# TEST_CPU.net
KiCad netlist of a schematic drawn in EAGLE
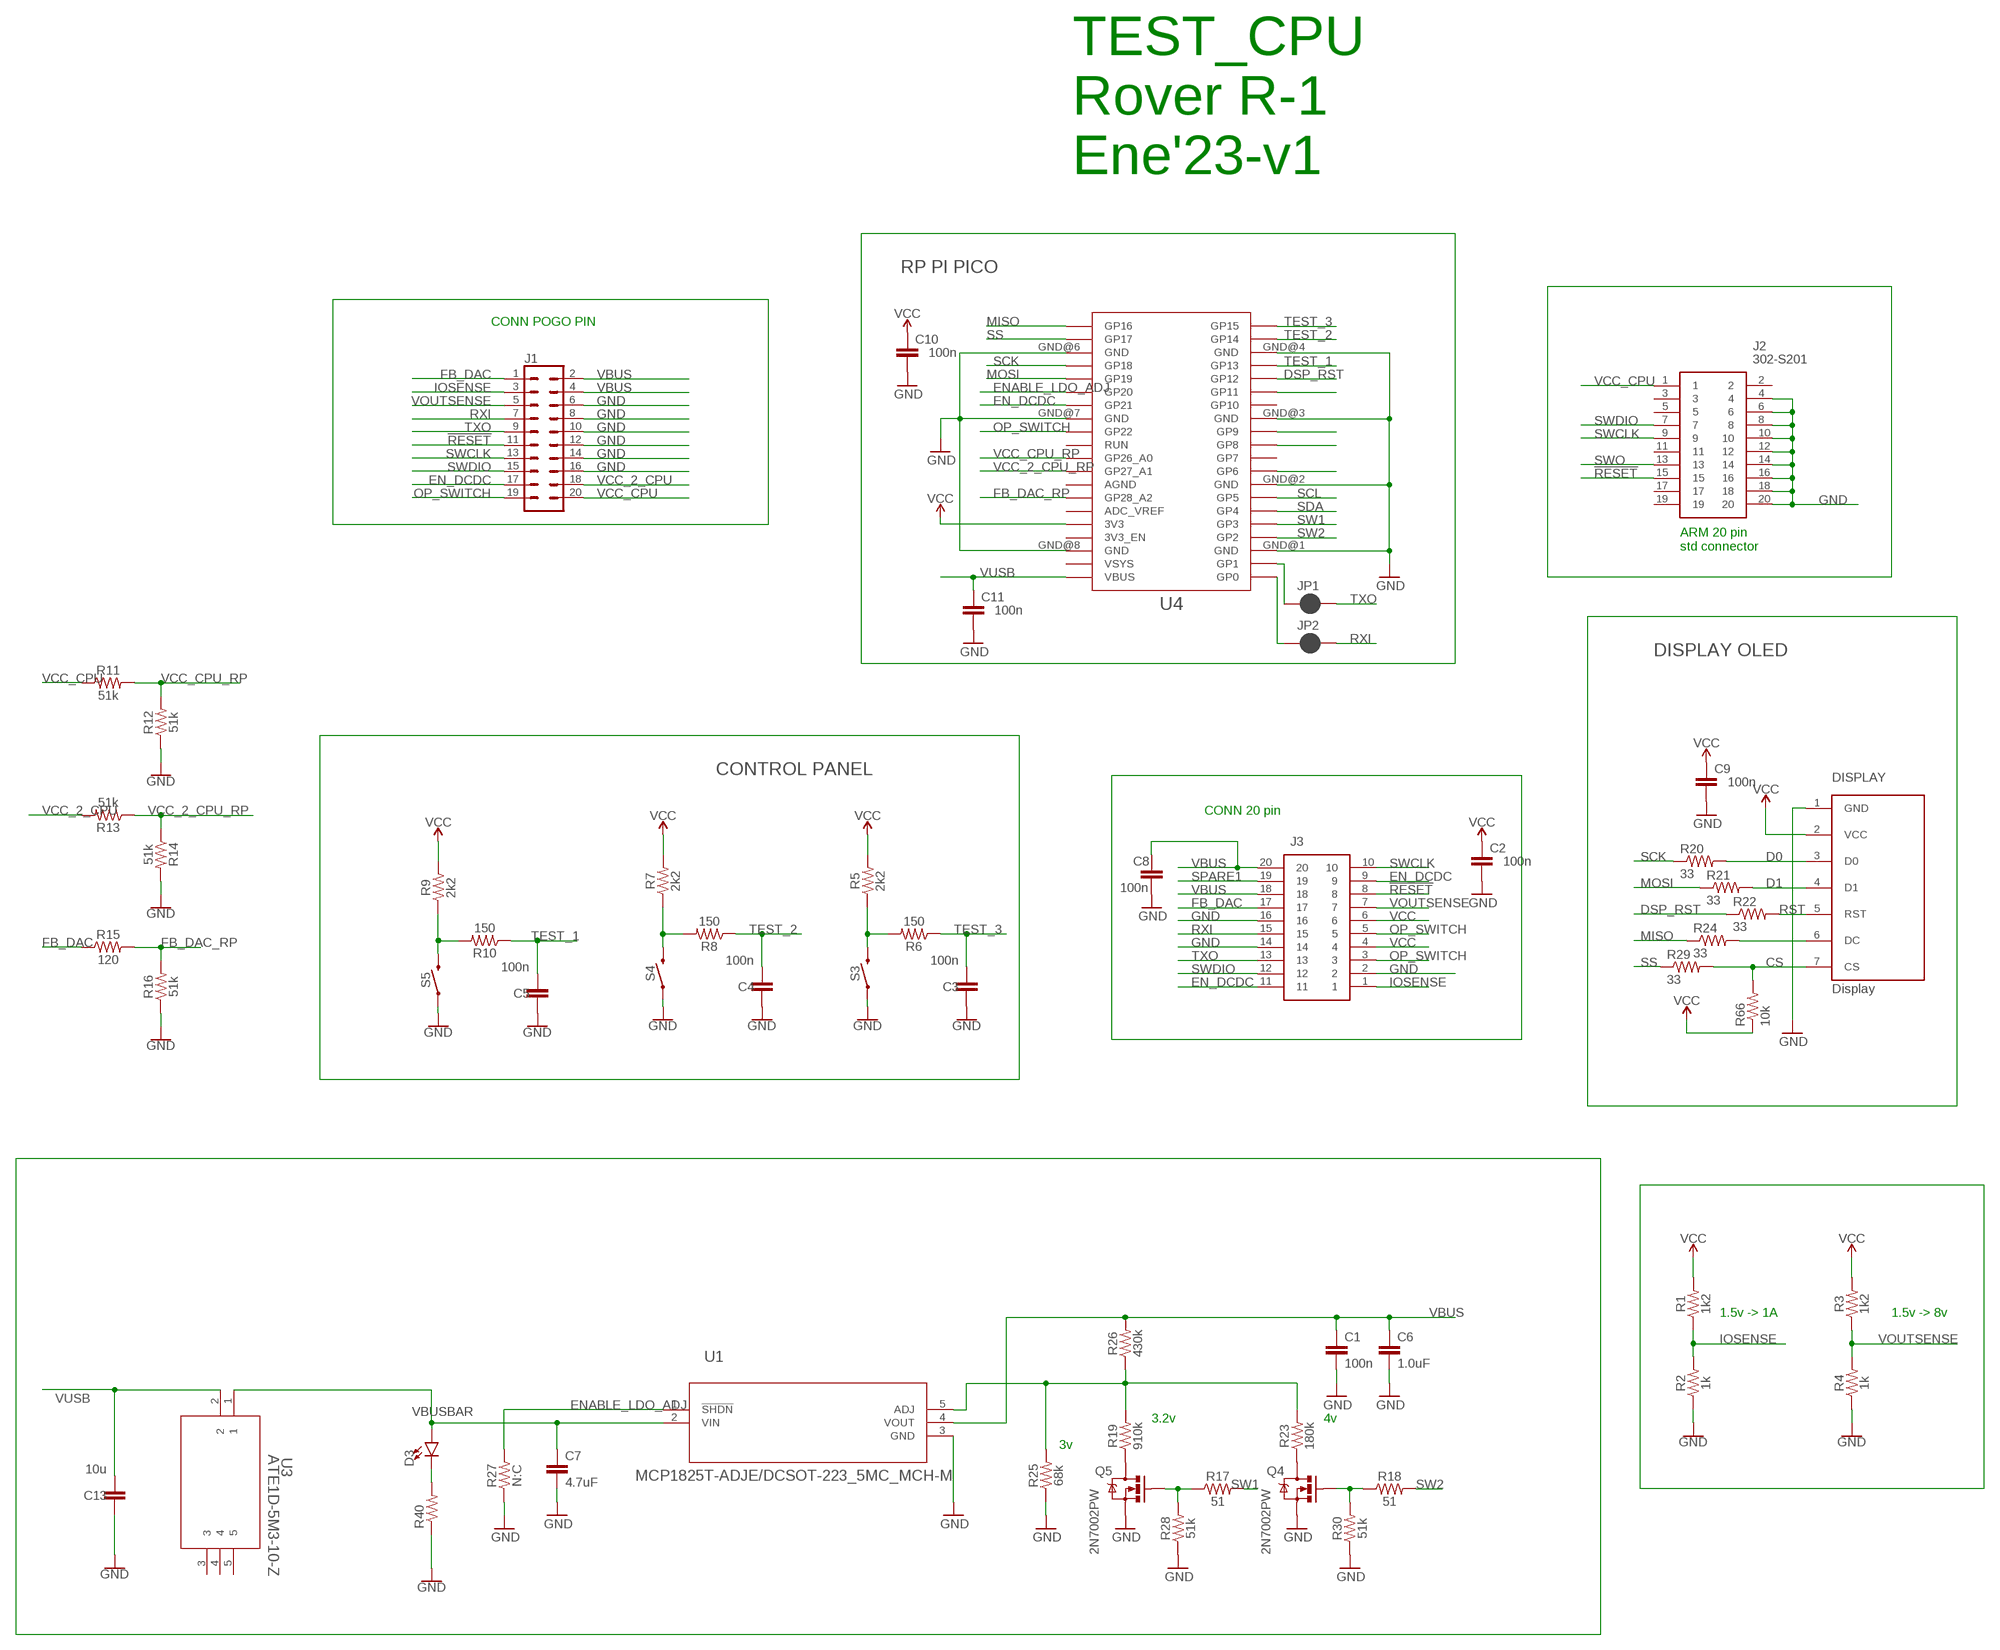
[diagram p0: schematic, sheet 1]

(export (version "E")
  (design (tool "Eeschema 10.0.6"))
  (components
    (comp (ref "C1")
      (value "100n")
      (footprint "eagle-import:0805")
      (libsource (lib "eagle-import") (part "1.0UF-0805-25V-(+80/-20%)"))
    )
    (comp (ref "C2")
      (value "100n")
      (footprint "eagle-import:0805")
      (libsource (lib "eagle-import") (part "1.0UF-0805-25V-(+80/-20%)"))
    )
    (comp (ref "C3")
      (value "100n")
      (footprint "eagle-import:0805")
      (libsource (lib "eagle-import") (part "1.0UF-0805-25V-(+80/-20%)"))
    )
    (comp (ref "C4")
      (value "100n")
      (footprint "eagle-import:0805")
      (libsource (lib "eagle-import") (part "1.0UF-0805-25V-(+80/-20%)"))
    )
    (comp (ref "C5")
      (value "100n")
      (footprint "eagle-import:0805")
      (libsource (lib "eagle-import") (part "1.0UF-0805-25V-(+80/-20%)"))
    )
    (comp (ref "C6")
      (value "1.0uF")
      (footprint "eagle-import:0805")
      (libsource (lib "eagle-import") (part "1.0UF-0805-25V-(+80/-20%)"))
    )
    (comp (ref "C7")
      (value "4.7uF")
      (footprint "eagle-import:0805")
      (libsource (lib "eagle-import") (part "1.0UF-0805-25V-(+80/-20%)"))
    )
    (comp (ref "C8")
      (value "100n")
      (footprint "eagle-import:0805")
      (libsource (lib "eagle-import") (part "1.0UF-0805-25V-(+80/-20%)"))
    )
    (comp (ref "C9")
      (value "100n")
      (footprint "eagle-import:0805")
      (libsource (lib "eagle-import") (part "1.0UF-0805-25V-(+80/-20%)"))
    )
    (comp (ref "C10")
      (value "100n")
      (footprint "eagle-import:0805")
      (libsource (lib "eagle-import") (part "1.0UF-0805-25V-(+80/-20%)"))
    )
    (comp (ref "C11")
      (value "100n")
      (footprint "eagle-import:0805")
      (libsource (lib "eagle-import") (part "1.0UF-0805-25V-(+80/-20%)"))
    )
    (comp (ref "C13")
      (value "10u")
      (footprint "eagle-import:0805")
      (libsource (lib "eagle-import") (part "1.0UF-0805-25V-(+80/-20%)"))
    )
    (comp (ref "D3")
      (value "LED3MM")
      (footprint "eagle-import:LED_3MM")
      (libsource (lib "eagle-import") (part "LED3MM"))
    )
    (comp (ref "DISPLAY")
      (value "Display")
      (footprint "eagle-import:OLED_LCD")
      (libsource (lib "eagle-import") (part "OLED_LCD"))
    )
    (comp (ref "J1")
      (value "CONN_10X2")
      (footprint "eagle-import:2X10")
      (libsource (lib "eagle-import") (part "CONN_10X2"))
    )
    (comp (ref "J2")
      (value "302-S201")
      (footprint "eagle-import:SHDR20W66P254_2X10_3300X905X90")
      (libsource (lib "eagle-import") (part "302-S201"))
    )
    (comp (ref "J3")
      (value "DF40C-20DP-0.4V_51_")
      (footprint "eagle-import:DF40C-20DPA")
      (fields
        (field (name "ARROW_PART_NUMBER") "DF40C-20DP-0.4V(51)")
        (field (name "MOUSER_PART_NUMBER") "798-DF40C20DP0.4V51")
      )
      (libsource (lib "eagle-import") (part "DF40C-20DP-0.4V_51_"))
    )
    (comp (ref "JP1")
      (value "JUMPER-SMT_2_NC_PASTE_SILK")
      (footprint "eagle-import:SMT-JUMPER_2_NC_PASTE_SILK")
      (libsource (lib "eagle-import") (part "JUMPER-SMT_2_NC_PASTE_SILK"))
    )
    (comp (ref "JP2")
      (value "JUMPER-SMT_2_NC_PASTE_SILK")
      (footprint "eagle-import:SMT-JUMPER_2_NC_PASTE_SILK")
      (libsource (lib "eagle-import") (part "JUMPER-SMT_2_NC_PASTE_SILK"))
    )
    (comp (ref "Q4")
      (value "2N7002PW")
      (footprint "eagle-import:SOT323")
      (libsource (lib "eagle-import") (part "MOSFET-NCHANNEL2N7002PW"))
    )
    (comp (ref "Q5")
      (value "2N7002PW")
      (footprint "eagle-import:SOT323")
      (libsource (lib "eagle-import") (part "MOSFET-NCHANNEL2N7002PW"))
    )
    (comp (ref "R1")
      (value "1k2")
      (footprint "eagle-import:0805")
      (libsource (lib "eagle-import") (part "RESISTOR0805"))
    )
    (comp (ref "R2")
      (value "1k")
      (footprint "eagle-import:0805")
      (libsource (lib "eagle-import") (part "RESISTOR0805"))
    )
    (comp (ref "R3")
      (value "1k2")
      (footprint "eagle-import:0805")
      (libsource (lib "eagle-import") (part "RESISTOR0805"))
    )
    (comp (ref "R4")
      (value "1k")
      (footprint "eagle-import:0805")
      (libsource (lib "eagle-import") (part "RESISTOR0805"))
    )
    (comp (ref "R5")
      (value "2k2")
      (footprint "eagle-import:0805")
      (libsource (lib "eagle-import") (part "RESISTOR0805"))
    )
    (comp (ref "R6")
      (value "150")
      (footprint "eagle-import:0805")
      (libsource (lib "eagle-import") (part "RESISTOR0805"))
    )
    (comp (ref "R7")
      (value "2k2")
      (footprint "eagle-import:0805")
      (libsource (lib "eagle-import") (part "RESISTOR0805"))
    )
    (comp (ref "R8")
      (value "150")
      (footprint "eagle-import:0805")
      (libsource (lib "eagle-import") (part "RESISTOR0805"))
    )
    (comp (ref "R9")
      (value "2k2")
      (footprint "eagle-import:0805")
      (libsource (lib "eagle-import") (part "RESISTOR0805"))
    )
    (comp (ref "R10")
      (value "150")
      (footprint "eagle-import:0805")
      (libsource (lib "eagle-import") (part "RESISTOR0805"))
    )
    (comp (ref "R11")
      (value "51k")
      (footprint "eagle-import:0805")
      (libsource (lib "eagle-import") (part "RESISTOR0805"))
    )
    (comp (ref "R12")
      (value "51k")
      (footprint "eagle-import:0805")
      (libsource (lib "eagle-import") (part "RESISTOR0805"))
    )
    (comp (ref "R13")
      (value "51k")
      (footprint "eagle-import:0805")
      (libsource (lib "eagle-import") (part "RESISTOR0805"))
    )
    (comp (ref "R14")
      (value "51k")
      (footprint "eagle-import:0805")
      (libsource (lib "eagle-import") (part "RESISTOR0805"))
    )
    (comp (ref "R15")
      (value "120")
      (footprint "eagle-import:0805")
      (libsource (lib "eagle-import") (part "RESISTOR0805"))
    )
    (comp (ref "R16")
      (value "51k")
      (footprint "eagle-import:0805")
      (libsource (lib "eagle-import") (part "RESISTOR0805"))
    )
    (comp (ref "R17")
      (value "51")
      (footprint "eagle-import:0805")
      (libsource (lib "eagle-import") (part "RESISTOR0805"))
    )
    (comp (ref "R18")
      (value "51")
      (footprint "eagle-import:0805")
      (libsource (lib "eagle-import") (part "RESISTOR0805"))
    )
    (comp (ref "R19")
      (value "910k")
      (footprint "eagle-import:0805")
      (libsource (lib "eagle-import") (part "RESISTOR0805"))
    )
    (comp (ref "R20")
      (value "33")
      (footprint "eagle-import:0805")
      (libsource (lib "eagle-import") (part "RESISTOR0805"))
    )
    (comp (ref "R21")
      (value "33")
      (footprint "eagle-import:0805")
      (libsource (lib "eagle-import") (part "RESISTOR0805"))
    )
    (comp (ref "R22")
      (value "33")
      (footprint "eagle-import:0805")
      (libsource (lib "eagle-import") (part "RESISTOR0805"))
    )
    (comp (ref "R23")
      (value "180k")
      (footprint "eagle-import:0805")
      (libsource (lib "eagle-import") (part "RESISTOR0805"))
    )
    (comp (ref "R24")
      (value "33")
      (footprint "eagle-import:0805")
      (libsource (lib "eagle-import") (part "RESISTOR0805"))
    )
    (comp (ref "R25")
      (value "68k")
      (footprint "eagle-import:0805")
      (libsource (lib "eagle-import") (part "RESISTOR0805"))
    )
    (comp (ref "R26")
      (value "430k")
      (footprint "eagle-import:0805")
      (libsource (lib "eagle-import") (part "RESISTOR0805"))
    )
    (comp (ref "R27")
      (value "N:C")
      (footprint "eagle-import:0805")
      (libsource (lib "eagle-import") (part "RESISTOR0805"))
    )
    (comp (ref "R28")
      (value "51k")
      (footprint "eagle-import:0805")
      (libsource (lib "eagle-import") (part "RESISTOR0805"))
    )
    (comp (ref "R29")
      (value "33")
      (footprint "eagle-import:0805")
      (libsource (lib "eagle-import") (part "RESISTOR0805"))
    )
    (comp (ref "R30")
      (value "51k")
      (footprint "eagle-import:0805")
      (libsource (lib "eagle-import") (part "RESISTOR0805"))
    )
    (comp (ref "R40")
      (value "360")
      (footprint "eagle-import:0805")
      (libsource (lib "eagle-import") (part "RESISTOR0805"))
    )
    (comp (ref "R66")
      (value "10k")
      (footprint "eagle-import:0805")
      (libsource (lib "eagle-import") (part "RESISTOR0805"))
    )
    (comp (ref "S3")
      (value "MOMENTARY-SWITCH-SPST-SMD-5.2MM")
      (footprint "eagle-import:TACTILE_SWITCH_SMD_5.2MM")
      (libsource (lib "eagle-import") (part "MOMENTARY-SWITCH-SPST-SMD-5.2MM"))
    )
    (comp (ref "S4")
      (value "MOMENTARY-SWITCH-SPST-SMD-5.2MM")
      (footprint "eagle-import:TACTILE_SWITCH_SMD_5.2MM")
      (libsource (lib "eagle-import") (part "MOMENTARY-SWITCH-SPST-SMD-5.2MM"))
    )
    (comp (ref "S5")
      (value "MOMENTARY-SWITCH-SPST-SMD-5.2MM")
      (footprint "eagle-import:TACTILE_SWITCH_SMD_5.2MM")
      (libsource (lib "eagle-import") (part "MOMENTARY-SWITCH-SPST-SMD-5.2MM"))
    )
    (comp (ref "U1")
      (value "MCP1825T-ADJE/DCSOT-223_5MC_MCH-M")
      (footprint "eagle-import:SOT-223_5MC_MCH-M")
      (fields (field (name "MANUFACTURER_PART_NUMBER") "MCP1825T-ADJE/DC"))
      (libsource (lib "eagle-import") (part "MCP1825T-ADJE/DCSOT-223_5MC_MCH-M"))
    )
    (comp (ref "U3")
      (value "ATE1D-5M3-10-Z")
      (footprint "eagle-import:SPDT05_ATE1D_9P5X8_NDC")
      (fields (field (name "COPYRIGHT") "Copyright (C) 2022 Ultra Librarian. All rights reserved."))
      (libsource (lib "eagle-import") (part "ATE1D-5M3-10-Z"))
    )
    (comp (ref "U4")
      (value "RPI_PICO_IG-TH")
      (footprint "eagle-import:RPI_PICO_TH")
      (libsource (lib "eagle-import") (part "RPI_PICO_IG-TH"))
    )
  )
  (nets
    (net (code "1") (name "/CS") (class "Default")
      (node (ref "DISPLAY") (pin "7") (pinfunction "CS_7") (pintype "bidirectional"))
      (node (ref "R29") (pin "2") (pinfunction "2_2") (pintype "passive"))
      (node (ref "R66") (pin "2") (pinfunction "2_2") (pintype "passive"))
    )
    (net (code "2") (name "/D0") (class "Default")
      (node (ref "DISPLAY") (pin "3") (pinfunction "D0_3") (pintype "bidirectional"))
      (node (ref "R20") (pin "2") (pinfunction "2_2") (pintype "passive"))
    )
    (net (code "3") (name "/D1") (class "Default")
      (node (ref "DISPLAY") (pin "4") (pinfunction "D1_4") (pintype "bidirectional"))
      (node (ref "R21") (pin "2") (pinfunction "2_2") (pintype "passive"))
    )
    (net (code "4") (name "/DSP_RST") (class "Default")
      (node (ref "R22") (pin "1") (pinfunction "1_1") (pintype "passive"))
      (node (ref "U4") (pin "GP12") (pinfunction "GP12_GP12") (pintype "bidirectional"))
    )
    (net (code "5") (name "/ENABLE_LDO_ADJ") (class "Default")
      (node (ref "R27") (pin "2") (pinfunction "2_2") (pintype "passive"))
      (node (ref "U1") (pin "1") (pinfunction "~{SHDN}_1") (pintype "passive"))
      (node (ref "U4") (pin "GP20") (pinfunction "GP20_GP20") (pintype "bidirectional"))
    )
    (net (code "6") (name "/EN_DCDC") (class "Default")
      (node (ref "J1") (pin "17") (pinfunction "17_17") (pintype "passive"))
      (node (ref "J3") (pin "11") (pinfunction "11_11") (pintype "bidirectional"))
      (node (ref "J3") (pin "9") (pinfunction "9_9") (pintype "bidirectional"))
      (node (ref "U4") (pin "GP21") (pinfunction "GP21_GP21") (pintype "bidirectional"))
    )
    (net (code "7") (name "/FB_DAC") (class "Default")
      (node (ref "J1") (pin "1") (pinfunction "1_1") (pintype "passive"))
      (node (ref "J3") (pin "17") (pinfunction "17_17") (pintype "bidirectional"))
      (node (ref "R15") (pin "1") (pinfunction "1_1") (pintype "passive"))
    )
    (net (code "8") (name "/FB_DAC_RP") (class "Default")
      (node (ref "R15") (pin "2") (pinfunction "2_2") (pintype "passive"))
      (node (ref "R16") (pin "2") (pinfunction "2_2") (pintype "passive"))
      (node (ref "U4") (pin "GP28_A2") (pinfunction "GP28_A2_GP28_A2") (pintype "bidirectional"))
    )
    (net (code "9") (name "/IOSENSE") (class "Default")
      (node (ref "J1") (pin "3") (pinfunction "3_3") (pintype "passive"))
      (node (ref "J3") (pin "1") (pinfunction "1_1") (pintype "bidirectional"))
      (node (ref "R1") (pin "1") (pinfunction "1_1") (pintype "passive"))
      (node (ref "R2") (pin "2") (pinfunction "2_2") (pintype "passive"))
    )
    (net (code "10") (name "/MISO") (class "Default")
      (node (ref "R24") (pin "1") (pinfunction "1_1") (pintype "passive"))
      (node (ref "U4") (pin "GP16") (pinfunction "GP16_GP16") (pintype "bidirectional"))
    )
    (net (code "11") (name "/MOSI") (class "Default")
      (node (ref "R21") (pin "1") (pinfunction "1_1") (pintype "passive"))
      (node (ref "U4") (pin "GP19") (pinfunction "GP19_GP19") (pintype "bidirectional"))
    )
    (net (code "12") (name "/OP_SWITCH") (class "Default")
      (node (ref "J1") (pin "19") (pinfunction "19_19") (pintype "passive"))
      (node (ref "J3") (pin "3") (pinfunction "3_3") (pintype "bidirectional"))
      (node (ref "J3") (pin "5") (pinfunction "5_5") (pintype "bidirectional"))
      (node (ref "U4") (pin "GP22") (pinfunction "GP22_GP22") (pintype "bidirectional"))
    )
    (net (code "13") (name "/RST") (class "Default")
      (node (ref "DISPLAY") (pin "5") (pinfunction "RST_5") (pintype "bidirectional"))
      (node (ref "R22") (pin "2") (pinfunction "2_2") (pintype "passive"))
    )
    (net (code "14") (name "/RXI") (class "Default")
      (node (ref "J1") (pin "7") (pinfunction "7_7") (pintype "passive"))
      (node (ref "J3") (pin "15") (pinfunction "15_15") (pintype "bidirectional"))
      (node (ref "JP2") (pin "2") (pinfunction "2_2") (pintype "passive"))
    )
    (net (code "15") (name "/SCK") (class "Default")
      (node (ref "R20") (pin "1") (pinfunction "1_1") (pintype "passive"))
      (node (ref "U4") (pin "GP18") (pinfunction "GP18_GP18") (pintype "bidirectional"))
    )
    (net (code "16") (name "/SCL") (class "Default")
      (node (ref "U4") (pin "GP5") (pinfunction "GP5_GP5") (pintype "bidirectional"))
    )
    (net (code "17") (name "/SDA") (class "Default")
      (node (ref "U4") (pin "GP4") (pinfunction "GP4_GP4") (pintype "bidirectional"))
    )
    (net (code "18") (name "/SPARE1") (class "Default")
      (node (ref "J3") (pin "19") (pinfunction "19_19") (pintype "bidirectional"))
    )
    (net (code "19") (name "/SS") (class "Default")
      (node (ref "R29") (pin "1") (pinfunction "1_1") (pintype "passive"))
      (node (ref "U4") (pin "GP17") (pinfunction "GP17_GP17") (pintype "bidirectional"))
    )
    (net (code "20") (name "/SW1") (class "Default")
      (node (ref "R17") (pin "2") (pinfunction "2_2") (pintype "passive"))
      (node (ref "U4") (pin "GP3") (pinfunction "GP3_GP3") (pintype "bidirectional"))
    )
    (net (code "21") (name "/SW2") (class "Default")
      (node (ref "R18") (pin "2") (pinfunction "2_2") (pintype "passive"))
      (node (ref "U4") (pin "GP2") (pinfunction "GP2_GP2") (pintype "bidirectional"))
    )
    (net (code "22") (name "/SWCLK") (class "Default")
      (node (ref "J1") (pin "13") (pinfunction "13_13") (pintype "passive"))
      (node (ref "J2") (pin "9") (pinfunction "9_9") (pintype "bidirectional"))
      (node (ref "J3") (pin "10") (pinfunction "10_10") (pintype "bidirectional"))
    )
    (net (code "23") (name "/SWDIO") (class "Default")
      (node (ref "J1") (pin "15") (pinfunction "15_15") (pintype "passive"))
      (node (ref "J2") (pin "7") (pinfunction "7_7") (pintype "bidirectional"))
      (node (ref "J3") (pin "12") (pinfunction "12_12") (pintype "bidirectional"))
    )
    (net (code "24") (name "/SWO") (class "Default")
      (node (ref "J2") (pin "13") (pinfunction "13_13") (pintype "bidirectional"))
    )
    (net (code "25") (name "/TEST_1") (class "Default")
      (node (ref "C5") (pin "2") (pinfunction "2_2") (pintype "passive"))
      (node (ref "R10") (pin "1") (pinfunction "1_1") (pintype "passive"))
      (node (ref "U4") (pin "GP13") (pinfunction "GP13_GP13") (pintype "bidirectional"))
    )
    (net (code "26") (name "/TEST_2") (class "Default")
      (node (ref "C4") (pin "2") (pinfunction "2_2") (pintype "passive"))
      (node (ref "R8") (pin "1") (pinfunction "1_1") (pintype "passive"))
      (node (ref "U4") (pin "GP14") (pinfunction "GP14_GP14") (pintype "bidirectional"))
    )
    (net (code "27") (name "/TEST_3") (class "Default")
      (node (ref "C3") (pin "2") (pinfunction "2_2") (pintype "passive"))
      (node (ref "R6") (pin "1") (pinfunction "1_1") (pintype "passive"))
      (node (ref "U4") (pin "GP15") (pinfunction "GP15_GP15") (pintype "bidirectional"))
    )
    (net (code "28") (name "/TXO") (class "Default")
      (node (ref "J1") (pin "9") (pinfunction "9_9") (pintype "passive"))
      (node (ref "J3") (pin "13") (pinfunction "13_13") (pintype "bidirectional"))
      (node (ref "JP1") (pin "2") (pinfunction "2_2") (pintype "passive"))
    )
    (net (code "29") (name "/VBUS") (class "Default")
      (node (ref "C1") (pin "1") (pinfunction "1_1") (pintype "passive"))
      (node (ref "C6") (pin "1") (pinfunction "1_1") (pintype "passive"))
      (node (ref "C8") (pin "1") (pinfunction "1_1") (pintype "passive"))
      (node (ref "J1") (pin "2") (pinfunction "2_2") (pintype "passive"))
      (node (ref "J1") (pin "4") (pinfunction "4_4") (pintype "passive"))
      (node (ref "J3") (pin "18") (pinfunction "18_18") (pintype "bidirectional"))
      (node (ref "J3") (pin "20") (pinfunction "20_20") (pintype "bidirectional"))
      (node (ref "R26") (pin "2") (pinfunction "2_2") (pintype "passive"))
      (node (ref "U1") (pin "4") (pinfunction "VOUT_4") (pintype "passive"))
    )
    (net (code "30") (name "/VBUSBAR") (class "Default")
      (node (ref "C7") (pin "1") (pinfunction "1_1") (pintype "passive"))
      (node (ref "D3") (pin "A") (pinfunction "A_A") (pintype "passive"))
      (node (ref "U1") (pin "2") (pinfunction "VIN_2") (pintype "passive"))
      (node (ref "U3") (pin "1") (pinfunction "1_1") (pintype "passive"))
    )
    (net (code "31") (name "/VCC_2_CPU") (class "Default")
      (node (ref "J1") (pin "18") (pinfunction "18_18") (pintype "passive"))
      (node (ref "R13") (pin "2") (pinfunction "2_2") (pintype "passive"))
    )
    (net (code "32") (name "/VCC_2_CPU_RP") (class "Default")
      (node (ref "R13") (pin "1") (pinfunction "1_1") (pintype "passive"))
      (node (ref "R14") (pin "1") (pinfunction "1_1") (pintype "passive"))
      (node (ref "U4") (pin "GP27_A1") (pinfunction "GP27_A1_GP27_A1") (pintype "bidirectional"))
    )
    (net (code "33") (name "/VCC_CPU") (class "Default")
      (node (ref "J1") (pin "20") (pinfunction "20_20") (pintype "passive"))
      (node (ref "J2") (pin "1") (pinfunction "1_1") (pintype "bidirectional"))
      (node (ref "R11") (pin "1") (pinfunction "1_1") (pintype "passive"))
    )
    (net (code "34") (name "/VCC_CPU_RP") (class "Default")
      (node (ref "R11") (pin "2") (pinfunction "2_2") (pintype "passive"))
      (node (ref "R12") (pin "2") (pinfunction "2_2") (pintype "passive"))
      (node (ref "U4") (pin "GP26_A0") (pinfunction "GP26_A0_GP26_A0") (pintype "bidirectional"))
    )
    (net (code "35") (name "/VOUTSENSE") (class "Default")
      (node (ref "J1") (pin "5") (pinfunction "5_5") (pintype "passive"))
      (node (ref "J3") (pin "7") (pinfunction "7_7") (pintype "bidirectional"))
      (node (ref "R3") (pin "1") (pinfunction "1_1") (pintype "passive"))
      (node (ref "R4") (pin "2") (pinfunction "2_2") (pintype "passive"))
    )
    (net (code "36") (name "/VUSB") (class "Default")
      (node (ref "C11") (pin "1") (pinfunction "1_1") (pintype "passive"))
      (node (ref "C13") (pin "2") (pinfunction "2_2") (pintype "passive"))
      (node (ref "U3") (pin "2") (pinfunction "2_2") (pintype "passive"))
      (node (ref "U4") (pin "VBUS") (pinfunction "VBUS_VBUS") (pintype "bidirectional"))
    )
    (net (code "37") (name "/~{RESET}") (class "Default")
      (node (ref "J1") (pin "11") (pinfunction "11_11") (pintype "passive"))
      (node (ref "J2") (pin "15") (pinfunction "15_15") (pintype "bidirectional"))
      (node (ref "J3") (pin "8") (pinfunction "8_8") (pintype "bidirectional"))
    )
    (net (code "38") (name "GND") (class "Default")
      (node (ref "C1") (pin "2") (pinfunction "2_2") (pintype "passive"))
      (node (ref "C10") (pin "2") (pinfunction "2_2") (pintype "passive"))
      (node (ref "C11") (pin "2") (pinfunction "2_2") (pintype "passive"))
      (node (ref "C13") (pin "1") (pinfunction "1_1") (pintype "passive"))
      (node (ref "C2") (pin "2") (pinfunction "2_2") (pintype "passive"))
      (node (ref "C3") (pin "1") (pinfunction "1_1") (pintype "passive"))
      (node (ref "C4") (pin "1") (pinfunction "1_1") (pintype "passive"))
      (node (ref "C5") (pin "1") (pinfunction "1_1") (pintype "passive"))
      (node (ref "C6") (pin "2") (pinfunction "2_2") (pintype "passive"))
      (node (ref "C7") (pin "2") (pinfunction "2_2") (pintype "passive"))
      (node (ref "C8") (pin "2") (pinfunction "2_2") (pintype "passive"))
      (node (ref "C9") (pin "2") (pinfunction "2_2") (pintype "passive"))
      (node (ref "DISPLAY") (pin "1") (pinfunction "GND_1") (pintype "bidirectional"))
      (node (ref "J1") (pin "10") (pinfunction "10_10") (pintype "passive"))
      (node (ref "J1") (pin "12") (pinfunction "12_12") (pintype "passive"))
      (node (ref "J1") (pin "14") (pinfunction "14_14") (pintype "passive"))
      (node (ref "J1") (pin "16") (pinfunction "16_16") (pintype "passive"))
      (node (ref "J1") (pin "6") (pinfunction "6_6") (pintype "passive"))
      (node (ref "J1") (pin "8") (pinfunction "8_8") (pintype "passive"))
      (node (ref "J2") (pin "10") (pinfunction "10_10") (pintype "bidirectional"))
      (node (ref "J2") (pin "12") (pinfunction "12_12") (pintype "bidirectional"))
      (node (ref "J2") (pin "14") (pinfunction "14_14") (pintype "bidirectional"))
      (node (ref "J2") (pin "16") (pinfunction "16_16") (pintype "bidirectional"))
      (node (ref "J2") (pin "18") (pinfunction "18_18") (pintype "bidirectional"))
      (node (ref "J2") (pin "20") (pinfunction "20_20") (pintype "bidirectional"))
      (node (ref "J2") (pin "4") (pinfunction "4_4") (pintype "bidirectional"))
      (node (ref "J2") (pin "6") (pinfunction "6_6") (pintype "bidirectional"))
      (node (ref "J2") (pin "8") (pinfunction "8_8") (pintype "bidirectional"))
      (node (ref "J3") (pin "14") (pinfunction "14_14") (pintype "bidirectional"))
      (node (ref "J3") (pin "16") (pinfunction "16_16") (pintype "bidirectional"))
      (node (ref "J3") (pin "2") (pinfunction "2_2") (pintype "bidirectional"))
      (node (ref "Q4") (pin "2") (pinfunction "S_2") (pintype "passive"))
      (node (ref "Q5") (pin "2") (pinfunction "S_2") (pintype "passive"))
      (node (ref "R12") (pin "1") (pinfunction "1_1") (pintype "passive"))
      (node (ref "R14") (pin "2") (pinfunction "2_2") (pintype "passive"))
      (node (ref "R16") (pin "1") (pinfunction "1_1") (pintype "passive"))
      (node (ref "R2") (pin "1") (pinfunction "1_1") (pintype "passive"))
      (node (ref "R25") (pin "1") (pinfunction "1_1") (pintype "passive"))
      (node (ref "R27") (pin "1") (pinfunction "1_1") (pintype "passive"))
      (node (ref "R28") (pin "1") (pinfunction "1_1") (pintype "passive"))
      (node (ref "R30") (pin "1") (pinfunction "1_1") (pintype "passive"))
      (node (ref "R4") (pin "1") (pinfunction "1_1") (pintype "passive"))
      (node (ref "R40") (pin "1") (pinfunction "1_1") (pintype "passive"))
      (node (ref "S3") (pin "1") (pinfunction "1_1") (pintype "passive"))
      (node (ref "S4") (pin "1") (pinfunction "1_1") (pintype "passive"))
      (node (ref "S5") (pin "1") (pinfunction "1_1") (pintype "passive"))
      (node (ref "U1") (pin "3") (pinfunction "GND_3") (pintype "passive"))
      (node (ref "U4") (pin "GND@1") (pinfunction "GND_GND@1") (pintype "bidirectional"))
      (node (ref "U4") (pin "GND@2") (pinfunction "GND_GND@2") (pintype "bidirectional"))
      (node (ref "U4") (pin "GND@3") (pinfunction "GND_GND@3") (pintype "bidirectional"))
      (node (ref "U4") (pin "GND@4") (pinfunction "GND_GND@4") (pintype "bidirectional"))
      (node (ref "U4") (pin "GND@6") (pinfunction "GND_GND@6") (pintype "bidirectional"))
      (node (ref "U4") (pin "GND@7") (pinfunction "GND_GND@7") (pintype "bidirectional"))
      (node (ref "U4") (pin "GND@8") (pinfunction "GND_GND@8") (pintype "bidirectional"))
    )
    (net (code "39") (name "Net-(D3-C)") (class "Default")
      (node (ref "D3") (pin "K") (pinfunction "C_K") (pintype "passive"))
      (node (ref "R40") (pin "2") (pinfunction "2_2") (pintype "passive"))
    )
    (net (code "40") (name "Net-(DISPLAY-DC)") (class "Default")
      (node (ref "DISPLAY") (pin "6") (pinfunction "DC_6") (pintype "bidirectional"))
      (node (ref "R24") (pin "2") (pinfunction "2_2") (pintype "passive"))
    )
    (net (code "41") (name "Net-(JP1-Pad1)") (class "Default")
      (node (ref "JP1") (pin "1") (pinfunction "1_1") (pintype "passive"))
      (node (ref "U4") (pin "GP1") (pinfunction "GP1_GP1") (pintype "bidirectional"))
    )
    (net (code "42") (name "Net-(JP2-Pad1)") (class "Default")
      (node (ref "JP2") (pin "1") (pinfunction "1_1") (pintype "passive"))
      (node (ref "U4") (pin "GP0") (pinfunction "GP0_GP0") (pintype "bidirectional"))
    )
    (net (code "43") (name "Net-(Q4-D)") (class "Default")
      (node (ref "Q4") (pin "3") (pinfunction "D_3") (pintype "passive"))
      (node (ref "R23") (pin "1") (pinfunction "1_1") (pintype "passive"))
    )
    (net (code "44") (name "Net-(Q4-G)") (class "Default")
      (node (ref "Q4") (pin "1") (pinfunction "G_1") (pintype "passive"))
      (node (ref "R18") (pin "1") (pinfunction "1_1") (pintype "passive"))
      (node (ref "R30") (pin "2") (pinfunction "2_2") (pintype "passive"))
    )
    (net (code "45") (name "Net-(Q5-D)") (class "Default")
      (node (ref "Q5") (pin "3") (pinfunction "D_3") (pintype "passive"))
      (node (ref "R19") (pin "1") (pinfunction "1_1") (pintype "passive"))
    )
    (net (code "46") (name "Net-(Q5-G)") (class "Default")
      (node (ref "Q5") (pin "1") (pinfunction "G_1") (pintype "passive"))
      (node (ref "R17") (pin "1") (pinfunction "1_1") (pintype "passive"))
      (node (ref "R28") (pin "2") (pinfunction "2_2") (pintype "passive"))
    )
    (net (code "47") (name "Net-(S3-2)") (class "Default")
      (node (ref "R5") (pin "1") (pinfunction "1_1") (pintype "passive"))
      (node (ref "R6") (pin "2") (pinfunction "2_2") (pintype "passive"))
      (node (ref "S3") (pin "3") (pinfunction "2_3") (pintype "passive"))
    )
    (net (code "48") (name "Net-(S4-2)") (class "Default")
      (node (ref "R7") (pin "1") (pinfunction "1_1") (pintype "passive"))
      (node (ref "R8") (pin "2") (pinfunction "2_2") (pintype "passive"))
      (node (ref "S4") (pin "3") (pinfunction "2_3") (pintype "passive"))
    )
    (net (code "49") (name "Net-(S5-2)") (class "Default")
      (node (ref "R10") (pin "2") (pinfunction "2_2") (pintype "passive"))
      (node (ref "R9") (pin "1") (pinfunction "1_1") (pintype "passive"))
      (node (ref "S5") (pin "3") (pinfunction "2_3") (pintype "passive"))
    )
    (net (code "50") (name "Net-(U1-ADJ)") (class "Default")
      (node (ref "R19") (pin "2") (pinfunction "2_2") (pintype "passive"))
      (node (ref "R23") (pin "2") (pinfunction "2_2") (pintype "passive"))
      (node (ref "R25") (pin "2") (pinfunction "2_2") (pintype "passive"))
      (node (ref "R26") (pin "1") (pinfunction "1_1") (pintype "passive"))
      (node (ref "U1") (pin "5") (pinfunction "ADJ_5") (pintype "passive"))
    )
    (net (code "51") (name "VCC") (class "Default")
      (node (ref "C10") (pin "1") (pinfunction "1_1") (pintype "passive"))
      (node (ref "C2") (pin "1") (pinfunction "1_1") (pintype "passive"))
      (node (ref "C9") (pin "1") (pinfunction "1_1") (pintype "passive"))
      (node (ref "DISPLAY") (pin "2") (pinfunction "VCC_2") (pintype "bidirectional"))
      (node (ref "J3") (pin "4") (pinfunction "4_4") (pintype "bidirectional"))
      (node (ref "J3") (pin "6") (pinfunction "6_6") (pintype "bidirectional"))
      (node (ref "R1") (pin "2") (pinfunction "2_2") (pintype "passive"))
      (node (ref "R3") (pin "2") (pinfunction "2_2") (pintype "passive"))
      (node (ref "R5") (pin "2") (pinfunction "2_2") (pintype "passive"))
      (node (ref "R66") (pin "1") (pinfunction "1_1") (pintype "passive"))
      (node (ref "R7") (pin "2") (pinfunction "2_2") (pintype "passive"))
      (node (ref "R9") (pin "2") (pinfunction "2_2") (pintype "passive"))
      (node (ref "U4") (pin "3V3") (pinfunction "3V3_3V3") (pintype "bidirectional"))
    )
    (net (code "52") (name "unconnected-(J2-Pad2)") (class "Default")
      (node (ref "J2") (pin "2") (pinfunction "2_2") (pintype "bidirectional"))
    )
    (net (code "53") (name "unconnected-(J2-Pad3)") (class "Default")
      (node (ref "J2") (pin "3") (pinfunction "3_3") (pintype "bidirectional"))
    )
    (net (code "54") (name "unconnected-(J2-Pad5)") (class "Default")
      (node (ref "J2") (pin "5") (pinfunction "5_5") (pintype "bidirectional"))
    )
    (net (code "55") (name "unconnected-(J2-Pad11)") (class "Default")
      (node (ref "J2") (pin "11") (pinfunction "11_11") (pintype "bidirectional"))
    )
    (net (code "56") (name "unconnected-(J2-Pad17)") (class "Default")
      (node (ref "J2") (pin "17") (pinfunction "17_17") (pintype "bidirectional"))
    )
    (net (code "57") (name "unconnected-(J2-Pad19)") (class "Default")
      (node (ref "J2") (pin "19") (pinfunction "19_19") (pintype "bidirectional"))
    )
    (net (code "58") (name "unconnected-(U3-Pad3)") (class "Default")
      (node (ref "U3") (pin "3") (pinfunction "3_3") (pintype "passive"))
    )
    (net (code "59") (name "unconnected-(U3-Pad4)") (class "Default")
      (node (ref "U3") (pin "4") (pinfunction "4_4") (pintype "passive"))
    )
    (net (code "60") (name "unconnected-(U3-Pad5)") (class "Default")
      (node (ref "U3") (pin "5") (pinfunction "5_5") (pintype "passive"))
    )
    (net (code "61") (name "unconnected-(U4-Pad3V3_EN)") (class "Default")
      (node (ref "U4") (pin "3V3_EN") (pinfunction "3V3_EN_3V3_EN") (pintype "bidirectional"))
    )
    (net (code "62") (name "unconnected-(U4-PadADC_VREF)") (class "Default")
      (node (ref "U4") (pin "ADC_VREF") (pinfunction "ADC_VREF_ADC_VREF") (pintype "bidirectional"))
    )
    (net (code "63") (name "unconnected-(U4-PadAGND)") (class "Default")
      (node (ref "U4") (pin "AGND") (pinfunction "AGND_AGND") (pintype "bidirectional"))
    )
    (net (code "64") (name "unconnected-(U4-PadGP6)") (class "Default")
      (node (ref "U4") (pin "GP6") (pinfunction "GP6_GP6") (pintype "bidirectional"))
    )
    (net (code "65") (name "unconnected-(U4-PadGP7)") (class "Default")
      (node (ref "U4") (pin "GP7") (pinfunction "GP7_GP7") (pintype "bidirectional"))
    )
    (net (code "66") (name "unconnected-(U4-PadGP8)") (class "Default")
      (node (ref "U4") (pin "GP8") (pinfunction "GP8_GP8") (pintype "bidirectional"))
    )
    (net (code "67") (name "unconnected-(U4-PadGP9)") (class "Default")
      (node (ref "U4") (pin "GP9") (pinfunction "GP9_GP9") (pintype "bidirectional"))
    )
    (net (code "68") (name "unconnected-(U4-PadGP10)") (class "Default")
      (node (ref "U4") (pin "GP10") (pinfunction "GP10_GP10") (pintype "bidirectional"))
    )
    (net (code "69") (name "unconnected-(U4-PadGP11)") (class "Default")
      (node (ref "U4") (pin "GP11") (pinfunction "GP11_GP11") (pintype "bidirectional"))
    )
    (net (code "70") (name "unconnected-(U4-PadRUN)") (class "Default")
      (node (ref "U4") (pin "RUN") (pinfunction "RUN_RUN") (pintype "bidirectional"))
    )
    (net (code "71") (name "unconnected-(U4-PadVSYS)") (class "Default")
      (node (ref "U4") (pin "VSYS") (pinfunction "VSYS_VSYS") (pintype "bidirectional"))
    )
  )
)
